# ESP8266_Schematic.net
KiCad netlist of a schematic drawn in Altium Designer
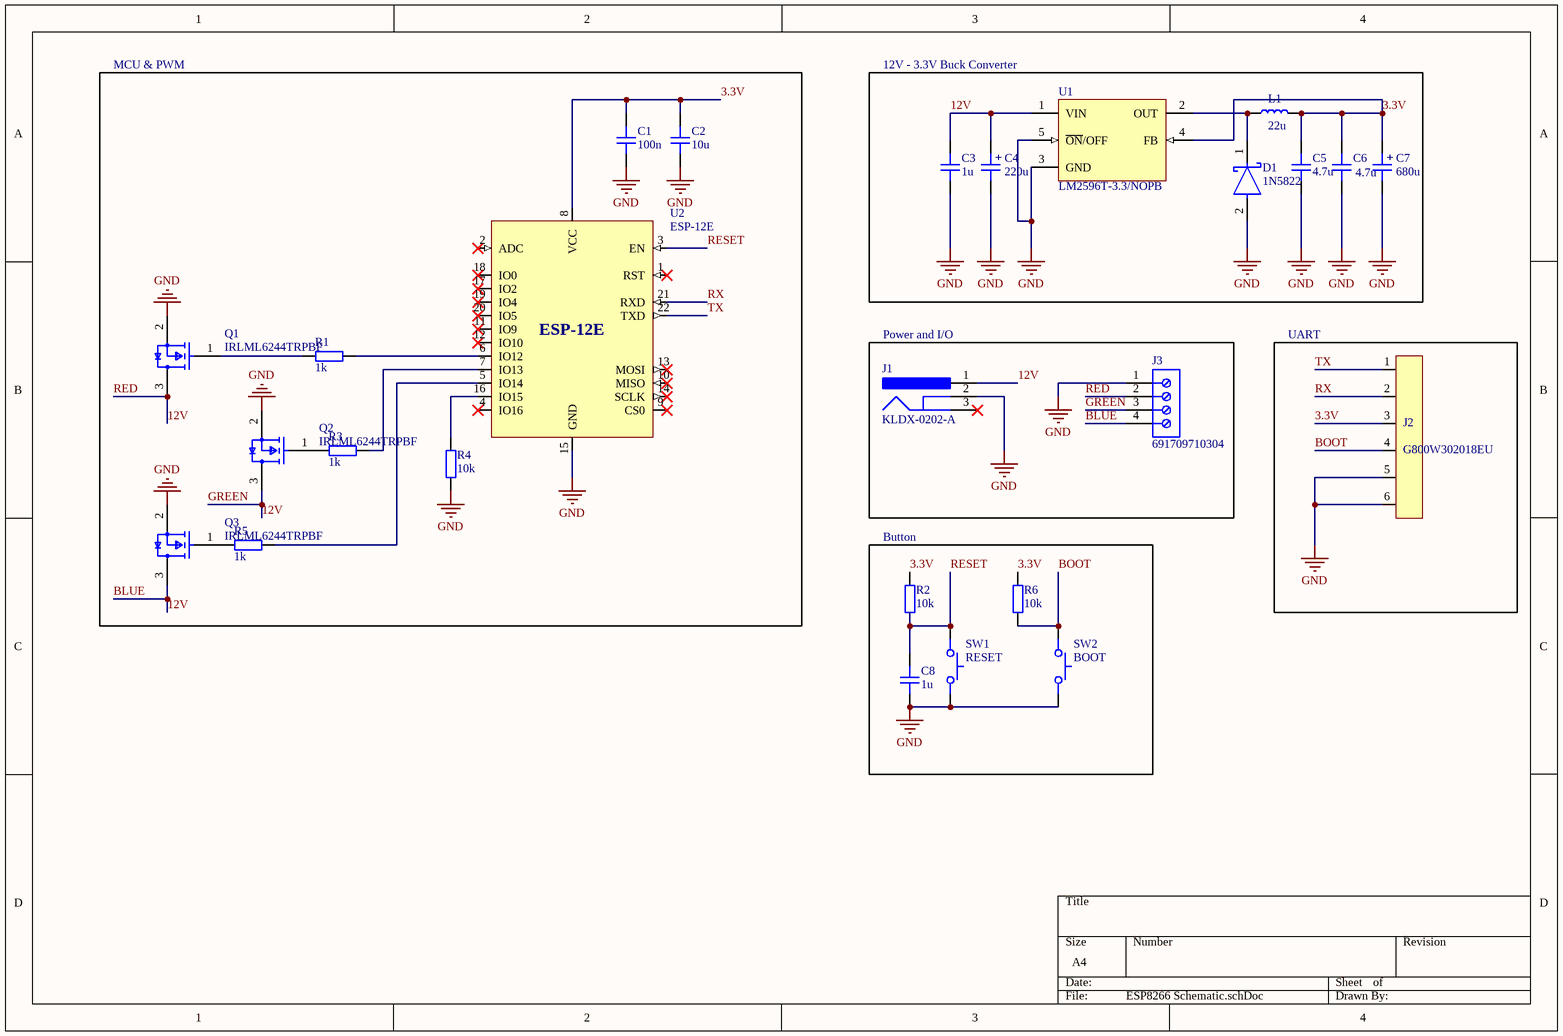
[diagram p0: ESP8266 Schematic.schDoc]

(export (version "E")
  (design (tool "Eeschema 10.0.6"))
  (components
    (comp (ref "C1")
      (value "100n")
      (footprint "CAP_0402")
      (description "Capacitor SMD 0402")
      (libsource (lib "*") (part "CAP_0402"))
    )
    (comp (ref "C2")
      (value "10u")
      (footprint "CAP_0402")
      (description "Capacitor SMD 0402")
      (libsource (lib "*") (part "CAP_0402"))
    )
    (comp (ref "C3")
      (value "1u")
      (footprint "CAP_0402")
      (description "Capacitor SMD 0402")
      (libsource (lib "*") (part "CAP_0402"))
    )
    (comp (ref "C4")
      (value "220u")
      (footprint "CAP_AE_SMD_D6MM3_H5M55")
      (description "Capacitor SMD Aluminium Electrolytic 6.3mm Diameter 5.5mm Height")
      (libsource (lib "*") (part "CAP_ALEL_6.3x5.5"))
    )
    (comp (ref "C5")
      (value "4.7u")
      (footprint "CAP_0402")
      (description "Capacitor SMD 0402")
      (libsource (lib "*") (part "CAP_0402"))
    )
    (comp (ref "C6")
      (value "4.7u")
      (footprint "CAP_0402")
      (description "Capacitor SMD 0402")
      (libsource (lib "*") (part "CAP_0402"))
    )
    (comp (ref "C7")
      (value "680u")
      (footprint "CAP_AE_SMD_D6MM3_H5M55")
      (description "Capacitor SMD Aluminium Electrolytic 6.3mm Diameter 5.5mm Height")
      (libsource (lib "*") (part "CAP_ALEL_6.3x5.5"))
    )
    (comp (ref "C8")
      (value "1u")
      (footprint "CAP_0402")
      (description "Capacitor SMD 0402")
      (libsource (lib "*") (part "CAP_0402"))
    )
    (comp (ref "D1")
      (value "1N5822")
      (footprint "FP-DO-201AD-MFG")
      (description "DIODE SCHOTTKY 40V 3A DO201AD")
      (fields
        (field (name "OCTOPART") "https://octopart.com/1n5822-stmicroelectronics-323225")
        (field (name "MANUFACTURER") "STMicroelectronics")
      )
      (libsource (lib "Altium Content Vault") (part "1d6ec82d83fb6aee721767c19dac4b9"))
    )
    (comp (ref "J1")
      (value "KLDX-0202-A")
      (footprint "KYCN-KLDX-0202-A_V")
      (description "DC Power Jack, 24 V, 3.5 A, -25 to 85 degC, 3-Pin THD, RoHS")
      (fields (field (name "MANUFACTURER") "Kycon"))
      (libsource (lib "Altium Content Vault") (part "JACK-2CD3-RN"))
    )
    (comp (ref "J2")
      (value "G800W302018EU")
      (footprint "G800W302018EU")
      (description "Pin Header 6 Position 2.54mm Pitch")
      (fields (field (name "MANUFACTURER") "Amphenol"))
      (libsource (lib "*") (part "G800W302018EU"))
    )
    (comp (ref "J3")
      (value "691709710304")
      (footprint "691709710304")
      (fields (field (name "VOLTAGE") "300V"))
      (libsource (lib "Altium Content Vault") (part "TBL - 1R - 04P - Screw"))
    )
    (comp (ref "L1")
      (value "22u")
      (footprint "IND_0402")
      (description "Inductor SMD 0402")
      (libsource (lib "*") (part "IND_0402"))
    )
    (comp (ref "Q1")
      (value "IRLML6244TRPBF")
      (footprint "FP-Micro3-IPC_C")
      (description "MOSFET N-CH 20V 6.3A SOT-23")
      (libsource (lib "Altium Content Vault") (part "3b9c635fedb024a5347a57b145af9cc"))
    )
    (comp (ref "Q2")
      (value "IRLML6244TRPBF")
      (footprint "FP-Micro3-IPC_C")
      (description "MOSFET N-CH 20V 6.3A SOT-23")
      (libsource (lib "Altium Content Vault") (part "3b9c635fedb024a5347a57b145af9cc"))
    )
    (comp (ref "Q3")
      (value "IRLML6244TRPBF")
      (footprint "FP-Micro3-IPC_C")
      (description "MOSFET N-CH 20V 6.3A SOT-23")
      (libsource (lib "Altium Content Vault") (part "3b9c635fedb024a5347a57b145af9cc"))
    )
    (comp (ref "R1")
      (value "1k")
      (footprint "RES_0201")
      (description "Resistor SMD 0201")
      (libsource (lib "*") (part "RES_0201"))
    )
    (comp (ref "R2")
      (value "10k")
      (footprint "RES_0201")
      (description "Resistor SMD 0201")
      (libsource (lib "*") (part "RES_0201"))
    )
    (comp (ref "R3")
      (value "1k")
      (footprint "RES_0201")
      (description "Resistor SMD 0201")
      (libsource (lib "*") (part "RES_0201"))
    )
    (comp (ref "R4")
      (value "10k")
      (footprint "RES_0201")
      (description "Resistor SMD 0201")
      (libsource (lib "*") (part "RES_0201"))
    )
    (comp (ref "R5")
      (value "1k")
      (footprint "RES_0201")
      (description "Resistor SMD 0201")
      (libsource (lib "*") (part "RES_0201"))
    )
    (comp (ref "R6")
      (value "10k")
      (footprint "RES_0201")
      (description "Resistor SMD 0201")
      (libsource (lib "*") (part "RES_0201"))
    )
    (comp (ref "SW1")
      (value "RESET")
      (footprint "SKRPANE010")
      (description "Tactile Switch SMD SPST")
      (fields
        (field (name "MANUFACTURER") "Alps Alpine")
        (field (name "MANUFACTURER PART NUMBER") "SKRPANE010")
      )
      (libsource (lib "*") (part "SKRPANE010"))
    )
    (comp (ref "SW2")
      (value "BOOT")
      (footprint "SKRPANE010")
      (description "Tactile Switch SMD SPST")
      (fields
        (field (name "MANUFACTURER") "Alps Alpine")
        (field (name "MANUFACTURER PART NUMBER") "SKRPANE010")
      )
      (libsource (lib "*") (part "SKRPANE010"))
    )
    (comp (ref "U1")
      (value "LM2596T-3.3/NOPB")
      (footprint "NDH0005A")
      (description "SIMPLE SWITCHER® Power Converter 150 KHz 3A Step-Down Voltage Regulator, 5-pin TO-220, Pb-Free")
      (fields (field (name "MANUFACTURER") "Texas Instruments"))
      (libsource (lib "Altium Content Vault") (part "PM-REG-LM2575HVT-12"))
    )
    (comp (ref "U2")
      (value "ESP-12E")
      (footprint "ESP-12E")
      (description "ESP8266 ESP-12E Module (ESP8266, Castellated Holes)")
      (fields (field (name "MANUFACTURER") "AI-THINKER"))
      (libsource (lib "*") (part "ESP-12E"))
    )
  )
  (nets
    (net (code "1") (name "/3.3V") (class "Default")
      (node (ref "C1") (pin "1") (pinfunction "1_1") (pintype "passive"))
      (node (ref "C2") (pin "1") (pinfunction "1_1") (pintype "passive"))
      (node (ref "C5") (pin "1") (pinfunction "1_1") (pintype "passive"))
      (node (ref "C6") (pin "1") (pinfunction "1_1") (pintype "passive"))
      (node (ref "C7") (pin "1") (pinfunction "1_1") (pintype "passive"))
      (node (ref "J2") (pin "3") (pinfunction "3_3") (pintype "passive"))
      (node (ref "L1") (pin "2") (pinfunction "2_2") (pintype "passive"))
      (node (ref "R2") (pin "2") (pinfunction "2_2") (pintype "passive"))
      (node (ref "R6") (pin "2") (pinfunction "2_2") (pintype "passive"))
      (node (ref "U1") (pin "4") (pinfunction "FB_4") (pintype "input"))
      (node (ref "U2") (pin "8") (pinfunction "VCC_8") (pintype "power_in"))
    )
    (net (code "2") (name "/12V") (class "Default")
      (node (ref "C3") (pin "1") (pinfunction "1_1") (pintype "passive"))
      (node (ref "C4") (pin "1") (pinfunction "1_1") (pintype "passive"))
      (node (ref "J1") (pin "1") (pinfunction "1_1") (pintype "passive"))
      (node (ref "J3") (pin "2") (pinfunction "2_2") (pintype "passive"))
      (node (ref "J3") (pin "3") (pinfunction "3_3") (pintype "passive"))
      (node (ref "J3") (pin "4") (pinfunction "4_4") (pintype "passive"))
      (node (ref "Q1") (pin "3") (pinfunction "D_3") (pintype "passive"))
      (node (ref "Q2") (pin "3") (pinfunction "D_3") (pintype "passive"))
      (node (ref "Q3") (pin "3") (pinfunction "D_3") (pintype "passive"))
      (node (ref "U1") (pin "1") (pinfunction "VIN_1") (pintype "power_in"))
    )
    (net (code "3") (name "/BOOT") (class "Default")
      (node (ref "J2") (pin "4") (pinfunction "4_4") (pintype "passive"))
      (node (ref "R6") (pin "1") (pinfunction "1_1") (pintype "passive"))
      (node (ref "SW2") (pin "12") (pintype "passive"))
    )
    (net (code "4") (name "/RESET") (class "Default")
      (node (ref "C8") (pin "1") (pinfunction "1_1") (pintype "passive"))
      (node (ref "R2") (pin "1") (pinfunction "1_1") (pintype "passive"))
      (node (ref "SW1") (pin "12") (pintype "passive"))
      (node (ref "U2") (pin "3") (pinfunction "EN_3") (pintype "input"))
    )
    (net (code "5") (name "/RX") (class "Default")
      (node (ref "J2") (pin "2") (pinfunction "2_2") (pintype "passive"))
      (node (ref "U2") (pin "21") (pinfunction "RXD_21") (pintype "input"))
    )
    (net (code "6") (name "/TX") (class "Default")
      (node (ref "J2") (pin "1") (pinfunction "1_1") (pintype "passive"))
      (node (ref "U2") (pin "22") (pinfunction "TXD_22") (pintype "output"))
    )
    (net (code "7") (name "GND") (class "Default")
      (node (ref "C1") (pin "2") (pinfunction "2_2") (pintype "passive"))
      (node (ref "C2") (pin "2") (pinfunction "2_2") (pintype "passive"))
      (node (ref "C3") (pin "2") (pinfunction "2_2") (pintype "passive"))
      (node (ref "C4") (pin "2") (pinfunction "2_2") (pintype "passive"))
      (node (ref "C5") (pin "2") (pinfunction "2_2") (pintype "passive"))
      (node (ref "C6") (pin "2") (pinfunction "2_2") (pintype "passive"))
      (node (ref "C7") (pin "2") (pinfunction "2_2") (pintype "passive"))
      (node (ref "C8") (pin "2") (pinfunction "2_2") (pintype "passive"))
      (node (ref "D1") (pin "2") (pinfunction "A_2") (pintype "passive"))
      (node (ref "J1") (pin "2") (pinfunction "2_2") (pintype "passive"))
      (node (ref "J2") (pin "5") (pinfunction "5_5") (pintype "passive"))
      (node (ref "J2") (pin "6") (pinfunction "6_6") (pintype "passive"))
      (node (ref "J3") (pin "1") (pinfunction "1_1") (pintype "passive"))
      (node (ref "Q1") (pin "2") (pinfunction "S_2") (pintype "passive"))
      (node (ref "Q2") (pin "2") (pinfunction "S_2") (pintype "passive"))
      (node (ref "Q3") (pin "2") (pinfunction "S_2") (pintype "passive"))
      (node (ref "R4") (pin "2") (pinfunction "2_2") (pintype "passive"))
      (node (ref "SW1") (pin "34") (pintype "passive"))
      (node (ref "SW2") (pin "34") (pintype "passive"))
      (node (ref "U1") (pin "3") (pinfunction "GND_3") (pintype "power_in"))
      (node (ref "U1") (pin "5") (pinfunction "~{ON}/OFF_5") (pintype "input"))
      (node (ref "U2") (pin "15") (pinfunction "GND_15") (pintype "power_in"))
    )
    (net (code "8") (name "Net-(D1-C)") (class "Default")
      (node (ref "D1") (pin "1") (pinfunction "C_1") (pintype "passive"))
      (node (ref "L1") (pin "1") (pinfunction "1_1") (pintype "passive"))
      (node (ref "U1") (pin "2") (pinfunction "OUT_2") (pintype "power_in"))
    )
    (net (code "9") (name "Net-(Q1-G)") (class "Default")
      (node (ref "Q1") (pin "1") (pinfunction "G_1") (pintype "passive"))
      (node (ref "R1") (pin "2") (pinfunction "2_2") (pintype "passive"))
    )
    (net (code "10") (name "Net-(Q2-G)") (class "Default")
      (node (ref "Q2") (pin "1") (pinfunction "G_1") (pintype "passive"))
      (node (ref "R3") (pin "2") (pinfunction "2_2") (pintype "passive"))
    )
    (net (code "11") (name "Net-(Q3-G)") (class "Default")
      (node (ref "Q3") (pin "1") (pinfunction "G_1") (pintype "passive"))
      (node (ref "R5") (pin "2") (pinfunction "2_2") (pintype "passive"))
    )
    (net (code "12") (name "Net-(U2-IO12)") (class "Default")
      (node (ref "R1") (pin "1") (pinfunction "1_1") (pintype "passive"))
      (node (ref "U2") (pin "6") (pinfunction "IO12_6") (pintype "bidirectional"))
    )
    (net (code "13") (name "Net-(U2-IO13)") (class "Default")
      (node (ref "R3") (pin "1") (pinfunction "1_1") (pintype "passive"))
      (node (ref "U2") (pin "7") (pinfunction "IO13_7") (pintype "bidirectional"))
    )
    (net (code "14") (name "Net-(U2-IO14)") (class "Default")
      (node (ref "R5") (pin "1") (pinfunction "1_1") (pintype "passive"))
      (node (ref "U2") (pin "5") (pinfunction "IO14_5") (pintype "bidirectional"))
    )
    (net (code "15") (name "Net-(U2-IO15)") (class "Default")
      (node (ref "R4") (pin "1") (pinfunction "1_1") (pintype "passive"))
      (node (ref "U2") (pin "16") (pinfunction "IO15_16") (pintype "bidirectional"))
    )
    (net (code "16") (name "unconnected-(J1-Pad3)") (class "Default")
      (node (ref "J1") (pin "3") (pinfunction "3_3") (pintype "passive+no_connect"))
    )
    (net (code "17") (name "unconnected-(U2-ADC-Pad2)") (class "Default")
      (node (ref "U2") (pin "2") (pinfunction "ADC_2") (pintype "input+no_connect"))
    )
    (net (code "18") (name "unconnected-(U2-CS0-Pad9)") (class "Default")
      (node (ref "U2") (pin "9") (pinfunction "CS0_9") (pintype "bidirectional+no_connect"))
    )
    (net (code "19") (name "unconnected-(U2-IO0-Pad18)") (class "Default")
      (node (ref "U2") (pin "18") (pinfunction "IO0_18") (pintype "bidirectional+no_connect"))
    )
    (net (code "20") (name "unconnected-(U2-IO2-Pad17)") (class "Default")
      (node (ref "U2") (pin "17") (pinfunction "IO2_17") (pintype "bidirectional+no_connect"))
    )
    (net (code "21") (name "unconnected-(U2-IO4-Pad19)") (class "Default")
      (node (ref "U2") (pin "19") (pinfunction "IO4_19") (pintype "bidirectional+no_connect"))
    )
    (net (code "22") (name "unconnected-(U2-IO5-Pad20)") (class "Default")
      (node (ref "U2") (pin "20") (pinfunction "IO5_20") (pintype "bidirectional+no_connect"))
    )
    (net (code "23") (name "unconnected-(U2-IO9-Pad11)") (class "Default")
      (node (ref "U2") (pin "11") (pinfunction "IO9_11") (pintype "bidirectional+no_connect"))
    )
    (net (code "24") (name "unconnected-(U2-IO10-Pad12)") (class "Default")
      (node (ref "U2") (pin "12") (pinfunction "IO10_12") (pintype "bidirectional+no_connect"))
    )
    (net (code "25") (name "unconnected-(U2-IO16-Pad4)") (class "Default")
      (node (ref "U2") (pin "4") (pinfunction "IO16_4") (pintype "bidirectional+no_connect"))
    )
    (net (code "26") (name "unconnected-(U2-MISO-Pad10)") (class "Default")
      (node (ref "U2") (pin "10") (pinfunction "MISO_10") (pintype "input+no_connect"))
    )
    (net (code "27") (name "unconnected-(U2-MOSI-Pad13)") (class "Default")
      (node (ref "U2") (pin "13") (pinfunction "MOSI_13") (pintype "output+no_connect"))
    )
    (net (code "28") (name "unconnected-(U2-RST-Pad1)") (class "Default")
      (node (ref "U2") (pin "1") (pinfunction "RST_1") (pintype "input+no_connect"))
    )
    (net (code "29") (name "unconnected-(U2-SCLK-Pad14)") (class "Default")
      (node (ref "U2") (pin "14") (pinfunction "SCLK_14") (pintype "output+no_connect"))
    )
  )
)
